# md.net
KiCad netlist of a schematic drawn in EAGLE
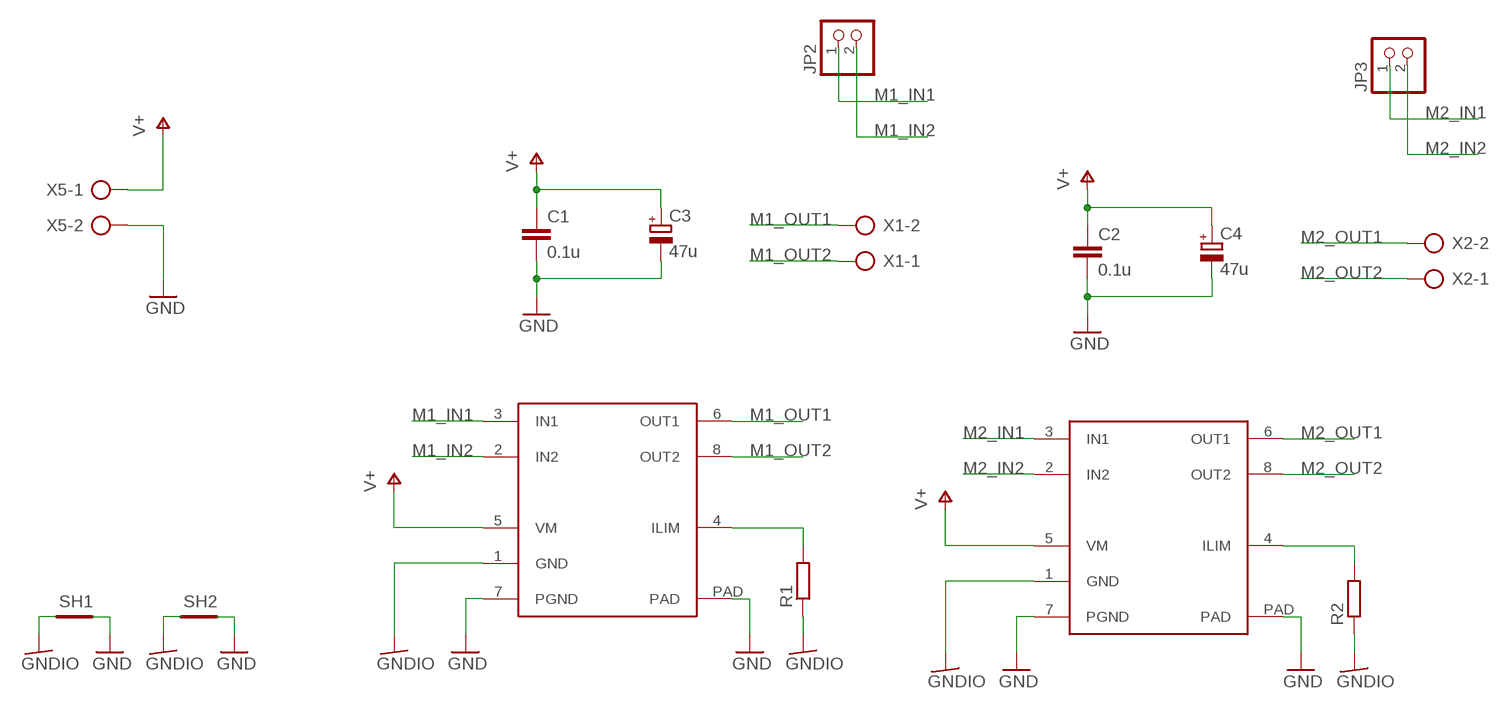
[diagram p0: schematic, sheet 1]

(export (version "E")
  (design (tool "Eeschema 10.0.6"))
  (components
    (comp (ref "C1")
      (value "0.1u")
      (footprint "eagle-import:C0805")
      (libsource (lib "eagle-import") (part "C-EUC0805"))
    )
    (comp (ref "C2")
      (value "0.1u")
      (footprint "eagle-import:C0805")
      (libsource (lib "eagle-import") (part "C-EUC0805"))
    )
    (comp (ref "C3")
      (value "47u")
      (footprint "eagle-import:E2,5-7")
      (libsource (lib "eagle-import") (part "CPOL-EUE2.5-7"))
    )
    (comp (ref "C4")
      (value "47u")
      (footprint "eagle-import:E2,5-7")
      (libsource (lib "eagle-import") (part "CPOL-EUE2.5-7"))
    )
    (comp (ref "JP2")
      (value "PINHD-1X2")
      (footprint "eagle-import:1X02")
      (libsource (lib "eagle-import") (part "PINHD-1X2"))
    )
    (comp (ref "JP3")
      (value "PINHD-1X2")
      (footprint "eagle-import:1X02")
      (libsource (lib "eagle-import") (part "PINHD-1X2"))
    )
    (comp (ref "MD1")
      (value "DRV8871")
      (footprint "eagle-import:SO8-COOL")
      (libsource (lib "eagle-import") (part "DRV8871"))
    )
    (comp (ref "MD2")
      (value "DRV8871")
      (footprint "eagle-import:SO8-COOL")
      (libsource (lib "eagle-import") (part "DRV8871"))
    )
    (comp (ref "R1")
      (value "R-EU_0207/7")
      (footprint "eagle-import:0207_7")
      (libsource (lib "eagle-import") (part "R-EU_0207/7"))
    )
    (comp (ref "R2")
      (value "R-EU_0207/7")
      (footprint "eagle-import:0207_7")
      (libsource (lib "eagle-import") (part "R-EU_0207/7"))
    )
    (comp (ref "SH1")
      (value "SHORTT5")
      (footprint "eagle-import:SHORT_TOP-50")
      (libsource (lib "eagle-import") (part "SHORTT5"))
    )
    (comp (ref "SH2")
      (value "SHORTT5")
      (footprint "eagle-import:SHORT_TOP-50")
      (libsource (lib "eagle-import") (part "SHORTT5"))
    )
    (comp (ref "X1")
      (value "AK300/2")
      (footprint "eagle-import:AK300_2")
      (libsource (lib "eagle-import") (part "AK300/2"))
    )
    (comp (ref "X2")
      (value "AK300/2")
      (footprint "eagle-import:AK300_2")
      (libsource (lib "eagle-import") (part "AK300/2"))
    )
    (comp (ref "X5")
      (value "AK300/2")
      (footprint "eagle-import:AK300_2")
      (libsource (lib "eagle-import") (part "AK300/2"))
    )
  )
  (nets
    (net (code "1") (name "/M1_IN1") (class "Default")
      (node (ref "JP2") (pin "1") (pinfunction "1_1") (pintype "passive"))
      (node (ref "MD1") (pin "3") (pinfunction "IN1_3") (pintype "bidirectional"))
    )
    (net (code "2") (name "/M1_IN2") (class "Default")
      (node (ref "JP2") (pin "2") (pinfunction "2_2") (pintype "passive"))
      (node (ref "MD1") (pin "2") (pinfunction "IN2_2") (pintype "bidirectional"))
    )
    (net (code "3") (name "/M1_OUT1") (class "Default")
      (node (ref "MD1") (pin "6") (pinfunction "OUT1_6") (pintype "bidirectional"))
      (node (ref "X1") (pin "2") (pinfunction "KL_2") (pintype "passive"))
    )
    (net (code "4") (name "/M1_OUT2") (class "Default")
      (node (ref "MD1") (pin "8") (pinfunction "OUT2_8") (pintype "bidirectional"))
      (node (ref "X1") (pin "1") (pinfunction "KL_1") (pintype "passive"))
    )
    (net (code "5") (name "/M2_IN1") (class "Default")
      (node (ref "JP3") (pin "1") (pinfunction "1_1") (pintype "passive"))
      (node (ref "MD2") (pin "3") (pinfunction "IN1_3") (pintype "bidirectional"))
    )
    (net (code "6") (name "/M2_IN2") (class "Default")
      (node (ref "JP3") (pin "2") (pinfunction "2_2") (pintype "passive"))
      (node (ref "MD2") (pin "2") (pinfunction "IN2_2") (pintype "bidirectional"))
    )
    (net (code "7") (name "/M2_OUT1") (class "Default")
      (node (ref "MD2") (pin "6") (pinfunction "OUT1_6") (pintype "bidirectional"))
      (node (ref "X2") (pin "2") (pinfunction "KL_2") (pintype "passive"))
    )
    (net (code "8") (name "/M2_OUT2") (class "Default")
      (node (ref "MD2") (pin "8") (pinfunction "OUT2_8") (pintype "bidirectional"))
      (node (ref "X2") (pin "1") (pinfunction "KL_1") (pintype "passive"))
    )
    (net (code "9") (name "GND") (class "Default")
      (node (ref "C1") (pin "2") (pinfunction "2_2") (pintype "passive"))
      (node (ref "C2") (pin "2") (pinfunction "2_2") (pintype "passive"))
      (node (ref "C3") (pin "-") (pinfunction "-_-") (pintype "passive"))
      (node (ref "C4") (pin "-") (pinfunction "-_-") (pintype "passive"))
      (node (ref "MD1") (pin "7") (pinfunction "PGND_7") (pintype "bidirectional"))
      (node (ref "MD1") (pin "PAD") (pinfunction "PAD_PAD") (pintype "bidirectional"))
      (node (ref "MD2") (pin "7") (pinfunction "PGND_7") (pintype "bidirectional"))
      (node (ref "MD2") (pin "PAD") (pinfunction "PAD_PAD") (pintype "bidirectional"))
      (node (ref "SH1") (pin "2") (pinfunction "P$2_2") (pintype "bidirectional"))
      (node (ref "SH2") (pin "2") (pinfunction "P$2_2") (pintype "bidirectional"))
      (node (ref "X5") (pin "2") (pinfunction "KL_2") (pintype "passive"))
    )
    (net (code "10") (name "GNDIO") (class "Default")
      (node (ref "MD1") (pin "1") (pinfunction "GND_1") (pintype "bidirectional"))
      (node (ref "MD2") (pin "1") (pinfunction "GND_1") (pintype "bidirectional"))
      (node (ref "R1") (pin "1") (pinfunction "1_1") (pintype "passive"))
      (node (ref "R2") (pin "1") (pinfunction "1_1") (pintype "passive"))
      (node (ref "SH1") (pin "1") (pinfunction "P$1_1") (pintype "bidirectional"))
      (node (ref "SH2") (pin "1") (pinfunction "P$1_1") (pintype "bidirectional"))
    )
    (net (code "11") (name "Net-(MD1-ILIM)") (class "Default")
      (node (ref "MD1") (pin "4") (pinfunction "ILIM_4") (pintype "bidirectional"))
      (node (ref "R1") (pin "2") (pinfunction "2_2") (pintype "passive"))
    )
    (net (code "12") (name "Net-(MD2-ILIM)") (class "Default")
      (node (ref "MD2") (pin "4") (pinfunction "ILIM_4") (pintype "bidirectional"))
      (node (ref "R2") (pin "2") (pinfunction "2_2") (pintype "passive"))
    )
    (net (code "13") (name "V+") (class "Default")
      (node (ref "C1") (pin "1") (pinfunction "1_1") (pintype "passive"))
      (node (ref "C2") (pin "1") (pinfunction "1_1") (pintype "passive"))
      (node (ref "C3") (pin "+") (pinfunction "+_+") (pintype "passive"))
      (node (ref "C4") (pin "+") (pinfunction "+_+") (pintype "passive"))
      (node (ref "MD1") (pin "5") (pinfunction "VM_5") (pintype "bidirectional"))
      (node (ref "MD2") (pin "5") (pinfunction "VM_5") (pintype "bidirectional"))
      (node (ref "X5") (pin "1") (pinfunction "KL_1") (pintype "passive"))
    )
  )
)
